# Adafruit_RP2040_CAN_Bus_Feather.net
KiCad netlist of a schematic drawn in EAGLE
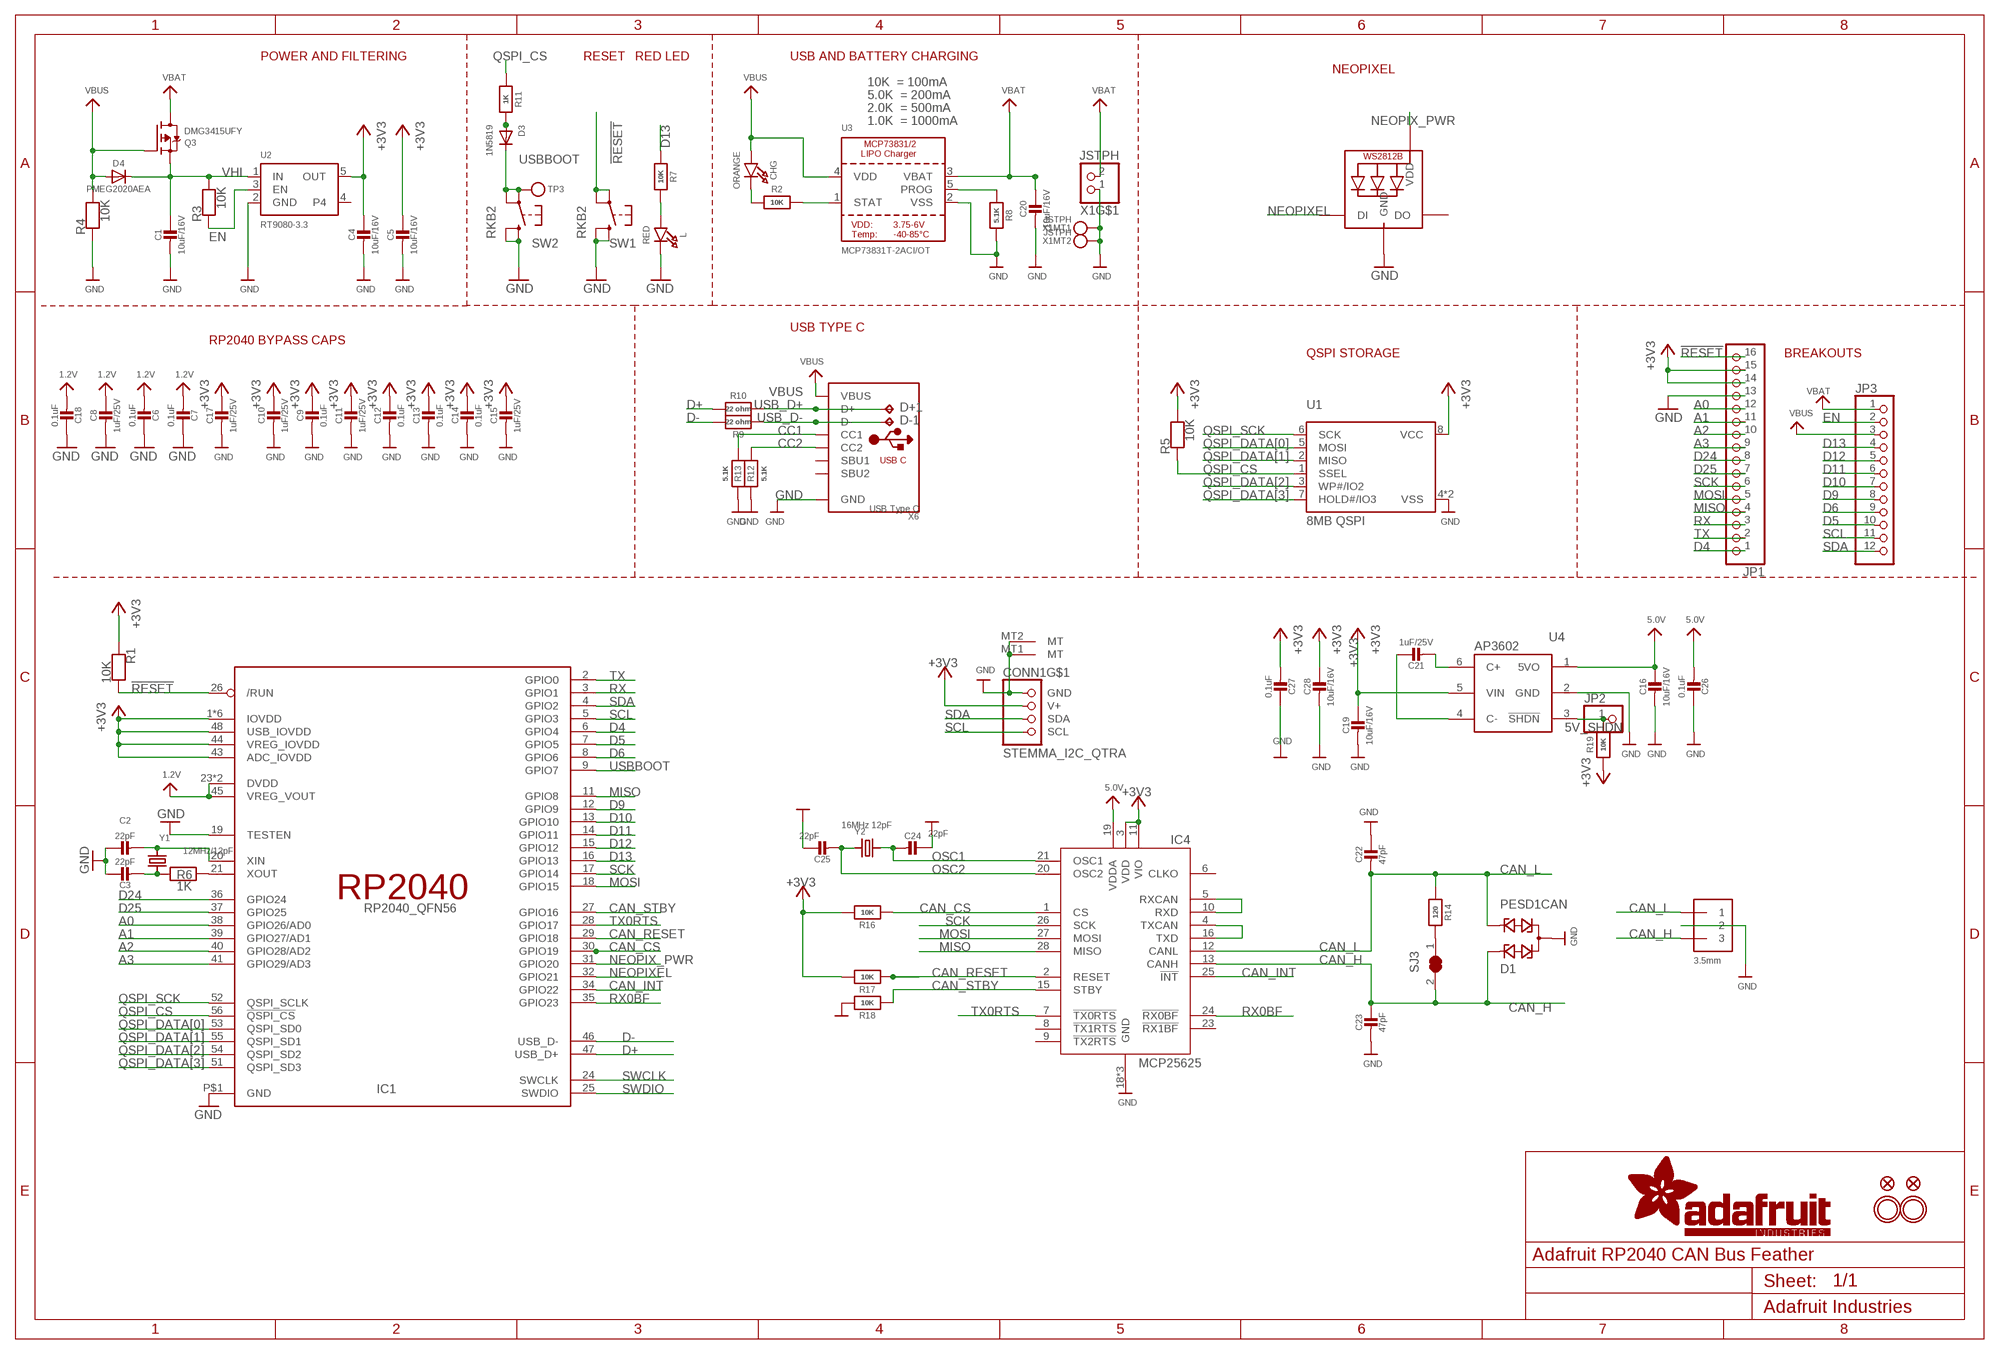
[diagram p0: schematic, sheet 1]

(export (version "E")
  (design (tool "Eeschema 10.0.6"))
  (components
    (comp (ref "C1")
      (value "10uF/16V")
      (footprint "eagle-import:0805-NO")
      (libsource (lib "eagle-import") (part "CAP_CERAMIC0805-NOOUTLINE"))
    )
    (comp (ref "C2")
      (value "22pF")
      (footprint "eagle-import:_0402NO")
      (libsource (lib "eagle-import") (part "CAP_CERAMIC_0402NO"))
    )
    (comp (ref "C3")
      (value "22pF")
      (footprint "eagle-import:_0402NO")
      (libsource (lib "eagle-import") (part "CAP_CERAMIC_0402NO"))
    )
    (comp (ref "C4")
      (value "10uF/16V")
      (footprint "eagle-import:0805-NO")
      (fields (field (name "REV") "A"))
      (libsource (lib "eagle-import") (part "CAP_CERAMIC0805-NOOUTLINE"))
    )
    (comp (ref "C5")
      (value "10uF/16V")
      (footprint "eagle-import:0805-NO")
      (libsource (lib "eagle-import") (part "CAP_CERAMIC0805-NOOUTLINE"))
    )
    (comp (ref "C6")
      (value "0.1uF")
      (footprint "eagle-import:_0402NO")
      (libsource (lib "eagle-import") (part "CAP_CERAMIC_0402NO"))
    )
    (comp (ref "C7")
      (value "0.1uF")
      (footprint "eagle-import:_0402NO")
      (libsource (lib "eagle-import") (part "CAP_CERAMIC_0402NO"))
    )
    (comp (ref "C8")
      (value "1uF/25V")
      (footprint "eagle-import:_0402NO")
      (libsource (lib "eagle-import") (part "CAP_CERAMIC_0402NO"))
    )
    (comp (ref "C9")
      (value "0.1uF")
      (footprint "eagle-import:_0402NO")
      (libsource (lib "eagle-import") (part "CAP_CERAMIC_0402NO"))
    )
    (comp (ref "C10")
      (value "1uF/25V")
      (footprint "eagle-import:_0402NO")
      (libsource (lib "eagle-import") (part "CAP_CERAMIC_0402NO"))
    )
    (comp (ref "C11")
      (value "1uF/25V")
      (footprint "eagle-import:_0402NO")
      (libsource (lib "eagle-import") (part "CAP_CERAMIC_0402NO"))
    )
    (comp (ref "C12")
      (value "0.1uF")
      (footprint "eagle-import:_0402NO")
      (libsource (lib "eagle-import") (part "CAP_CERAMIC_0402NO"))
    )
    (comp (ref "C13")
      (value "0.1uF")
      (footprint "eagle-import:_0402NO")
      (libsource (lib "eagle-import") (part "CAP_CERAMIC_0402NO"))
    )
    (comp (ref "C14")
      (value "0.1uF")
      (footprint "eagle-import:_0402NO")
      (libsource (lib "eagle-import") (part "CAP_CERAMIC_0402NO"))
    )
    (comp (ref "C15")
      (value "1uF/25V")
      (footprint "eagle-import:_0402NO")
      (libsource (lib "eagle-import") (part "CAP_CERAMIC_0402NO"))
    )
    (comp (ref "C16")
      (value "10uF/16V")
      (footprint "eagle-import:0805-NO")
      (libsource (lib "eagle-import") (part "CAP_CERAMIC0805-NOOUTLINE"))
    )
    (comp (ref "C17")
      (value "1uF/25V")
      (footprint "eagle-import:_0402NO")
      (libsource (lib "eagle-import") (part "CAP_CERAMIC_0402NO"))
    )
    (comp (ref "C18")
      (value "0.1uF")
      (footprint "eagle-import:_0402NO")
      (libsource (lib "eagle-import") (part "CAP_CERAMIC_0402NO"))
    )
    (comp (ref "C19")
      (value "10uF/16V")
      (footprint "eagle-import:0805-NO")
      (libsource (lib "eagle-import") (part "CAP_CERAMIC0805-NOOUTLINE"))
    )
    (comp (ref "C20")
      (value "10uF/16V")
      (footprint "eagle-import:0805-NO")
      (libsource (lib "eagle-import") (part "CAP_CERAMIC0805-NOOUTLINE"))
    )
    (comp (ref "C21")
      (value "1uF/25V")
      (footprint "eagle-import:_0402NO")
      (libsource (lib "eagle-import") (part "CAP_CERAMIC_0402NO"))
    )
    (comp (ref "C22")
      (value "47pF")
      (footprint "eagle-import:_0402NO")
      (libsource (lib "eagle-import") (part "CAP_CERAMIC_0402NO"))
    )
    (comp (ref "C23")
      (value "47pF")
      (footprint "eagle-import:_0402NO")
      (libsource (lib "eagle-import") (part "CAP_CERAMIC_0402NO"))
    )
    (comp (ref "C24")
      (value "22pF")
      (footprint "eagle-import:_0402NO")
      (libsource (lib "eagle-import") (part "CAP_CERAMIC_0402NO"))
    )
    (comp (ref "C25")
      (value "22pF")
      (footprint "eagle-import:_0402NO")
      (libsource (lib "eagle-import") (part "CAP_CERAMIC_0402NO"))
    )
    (comp (ref "C26")
      (value "0.1uF")
      (footprint "eagle-import:_0402NO")
      (libsource (lib "eagle-import") (part "CAP_CERAMIC_0402NO"))
    )
    (comp (ref "C27")
      (value "0.1uF")
      (footprint "eagle-import:_0402NO")
      (libsource (lib "eagle-import") (part "CAP_CERAMIC_0402NO"))
    )
    (comp (ref "C28")
      (value "10uF/16V")
      (footprint "eagle-import:0805-NO")
      (libsource (lib "eagle-import") (part "CAP_CERAMIC0805-NOOUTLINE"))
    )
    (comp (ref "CHG")
      (value "ORANGE")
      (footprint "eagle-import:CHIPLED_0603_NOOUTLINE")
      (libsource (lib "eagle-import") (part "LED0603_NOOUTLINE"))
    )
    (comp (ref "CONN1")
      (value "STEMMA_I2C_QTRA")
      (footprint "eagle-import:JST_SH4_RA")
      (libsource (lib "eagle-import") (part "STEMMA_I2C_QTRA"))
    )
    (comp (ref "D+1")
      (value "TPB1,27")
      (footprint "eagle-import:B1,27")
      (libsource (lib "eagle-import") (part "TPB1,27"))
    )
    (comp (ref "D-1")
      (value "TPB1,27")
      (footprint "eagle-import:B1,27")
      (libsource (lib "eagle-import") (part "TPB1,27"))
    )
    (comp (ref "D1")
      (value "PESD1CAN")
      (footprint "eagle-import:SOT23")
      (libsource (lib "eagle-import") (part "PESD1CAN"))
    )
    (comp (ref "D3")
      (value "1N5819")
      (footprint "eagle-import:SOD-323_MINI")
      (libsource (lib "eagle-import") (part "DIODE_SOD323MINI"))
    )
    (comp (ref "D4")
      (value "PMEG2020AEA")
      (footprint "eagle-import:SOD-323F")
      (libsource (lib "eagle-import") (part "DIODESOD-323F"))
    )
    (comp (ref "IC1")
      (value "RP2040_QFN56")
      (footprint "eagle-import:QFN56_7MM_REDUCEDEPAD")
      (libsource (lib "eagle-import") (part "RP2040_QFN56"))
    )
    (comp (ref "IC4")
      (value "MCP25625")
      (footprint "eagle-import:QFN28-ML_6X6MM")
      (libsource (lib "eagle-import") (part "MCP25625"))
    )
    (comp (ref "JP1")
      (value "HEADER-1X16ROUND")
      (footprint "eagle-import:1X16_ROUND")
      (libsource (lib "eagle-import") (part "HEADER-1X16ROUND"))
    )
    (comp (ref "JP2")
      (value "HEADER-1X12MM")
      (footprint "eagle-import:1X01_2MM")
      (libsource (lib "eagle-import") (part "HEADER-1X12MM"))
    )
    (comp (ref "JP3")
      (value "HEADER-1X12")
      (footprint "eagle-import:1X12_ROUND")
      (libsource (lib "eagle-import") (part "HEADER-1X12"))
    )
    (comp (ref "L")
      (value "RED")
      (footprint "eagle-import:CHIPLED_0603_NOOUTLINE")
      (libsource (lib "eagle-import") (part "LED0603_NOOUTLINE"))
    )
    (comp (ref "LED1")
      (value "WS2812B_SK6805_1515")
      (footprint "eagle-import:SK6805_1515")
      (libsource (lib "eagle-import") (part "WS2812B_SK6805_1515"))
    )
    (comp (ref "NEOPIX1")
      (value "3.5mm")
      (footprint "eagle-import:TERMBLOCK_1X3-3.5MM")
      (libsource (lib "eagle-import") (part "TERMBLOCK_1X3"))
    )
    (comp (ref "Q3")
      (value "DMG3415UFY")
      (footprint "eagle-import:DFN2015-3")
      (libsource (lib "eagle-import") (part "MOSFET-P_DFN2015"))
    )
    (comp (ref "R1")
      (value "10K")
      (footprint "eagle-import:_0402NO")
      (libsource (lib "eagle-import") (part "RESISTOR_0402NO"))
    )
    (comp (ref "R2")
      (value "10K")
      (footprint "eagle-import:_0402NO")
      (libsource (lib "eagle-import") (part "RESISTOR_0402NO"))
    )
    (comp (ref "R3")
      (value "10K")
      (footprint "eagle-import:_0402NO")
      (libsource (lib "eagle-import") (part "RESISTOR_0402NO"))
    )
    (comp (ref "R4")
      (value "10K")
      (footprint "eagle-import:_0402NO")
      (libsource (lib "eagle-import") (part "RESISTOR_0402NO"))
    )
    (comp (ref "R5")
      (value "10K")
      (footprint "eagle-import:_0402NO")
      (libsource (lib "eagle-import") (part "RESISTOR_0402NO"))
    )
    (comp (ref "R6")
      (value "1K")
      (footprint "eagle-import:_0402NO")
      (libsource (lib "eagle-import") (part "RESISTOR_0402NO"))
    )
    (comp (ref "R7")
      (value "10K")
      (footprint "eagle-import:_0402NO")
      (libsource (lib "eagle-import") (part "RESISTOR_0402NO"))
    )
    (comp (ref "R8")
      (value "5.1K")
      (footprint "eagle-import:_0402NO")
      (libsource (lib "eagle-import") (part "RESISTOR_0402NO"))
    )
    (comp (ref "R9")
      (value "22 ohm")
      (footprint "eagle-import:_0402NO")
      (libsource (lib "eagle-import") (part "RESISTOR_0402NO"))
    )
    (comp (ref "R10")
      (value "22 ohm")
      (footprint "eagle-import:_0402NO")
      (libsource (lib "eagle-import") (part "RESISTOR_0402NO"))
    )
    (comp (ref "R11")
      (value "1K")
      (footprint "eagle-import:_0402NO")
      (libsource (lib "eagle-import") (part "RESISTOR_0402NO"))
    )
    (comp (ref "R12")
      (value "5.1K")
      (footprint "eagle-import:_0402NO")
      (libsource (lib "eagle-import") (part "RESISTOR_0402NO"))
    )
    (comp (ref "R13")
      (value "5.1K")
      (footprint "eagle-import:_0402NO")
      (libsource (lib "eagle-import") (part "RESISTOR_0402NO"))
    )
    (comp (ref "R14")
      (value "120")
      (footprint "eagle-import:_0402NO")
      (libsource (lib "eagle-import") (part "RESISTOR_0402NO"))
    )
    (comp (ref "R16")
      (value "10K")
      (footprint "eagle-import:_0402NO")
      (libsource (lib "eagle-import") (part "RESISTOR_0402NO"))
    )
    (comp (ref "R17")
      (value "10K")
      (footprint "eagle-import:_0402NO")
      (libsource (lib "eagle-import") (part "RESISTOR_0402NO"))
    )
    (comp (ref "R18")
      (value "10K")
      (footprint "eagle-import:_0402NO")
      (libsource (lib "eagle-import") (part "RESISTOR_0402NO"))
    )
    (comp (ref "R19")
      (value "10K")
      (footprint "eagle-import:_0402NO")
      (libsource (lib "eagle-import") (part "RESISTOR_0402NO"))
    )
    (comp (ref "SJ3")
      (value "SOLDERJUMPER_CLOSED")
      (footprint "eagle-import:SOLDERJUMPER_CLOSEDWIRE")
      (libsource (lib "eagle-import") (part "SOLDERJUMPER_CLOSED"))
    )
    (comp (ref "SW1")
      (value "RKB2")
      (footprint "eagle-import:BTN_RKB2_4.6X2.8")
      (libsource (lib "eagle-import") (part "SWITCH_TACT_SMT_RKB2"))
    )
    (comp (ref "SW2")
      (value "RKB2")
      (footprint "eagle-import:BTN_RKB2_4.6X2.8")
      (libsource (lib "eagle-import") (part "SWITCH_TACT_SMT_RKB2"))
    )
    (comp (ref "TP3")
      (value "TESTPOINTROUND1.5MMNO")
      (footprint "eagle-import:TESTPOINT_ROUND_1.5MM_NO")
      (libsource (lib "eagle-import") (part "TESTPOINTROUND1.5MMNO"))
    )
    (comp (ref "U$31")
      (value "MOUNTINGHOLE2.5")
      (footprint "eagle-import:MOUNTINGHOLE_2.5_PLATED")
      (libsource (lib "eagle-import") (part "MOUNTINGHOLE2.5"))
    )
    (comp (ref "U$32")
      (value "MOUNTINGHOLE2.5")
      (footprint "eagle-import:MOUNTINGHOLE_2.5_PLATED")
      (libsource (lib "eagle-import") (part "MOUNTINGHOLE2.5"))
    )
    (comp (ref "U$34")
      (value "FIDUCIAL_1MM")
      (footprint "eagle-import:FIDUCIAL_1MM")
      (libsource (lib "eagle-import") (part "FIDUCIAL_1MM"))
    )
    (comp (ref "U$35")
      (value "FIDUCIAL_1MM")
      (footprint "eagle-import:FIDUCIAL_1MM")
      (libsource (lib "eagle-import") (part "FIDUCIAL_1MM"))
    )
    (comp (ref "U1")
      (value "8MB QSPI")
      (footprint "eagle-import:USON8_4X4")
      (libsource (lib "eagle-import") (part "SPIFLASH_8PIN_4X4"))
    )
    (comp (ref "U2")
      (value "RT9080-3.3")
      (footprint "eagle-import:SOT23-5")
      (fields (field (name "JLC_ROTATION") "0"))
      (libsource (lib "eagle-import") (part "VREG_SOT23-5"))
    )
    (comp (ref "U3")
      (value "MCP73831T-2ACI/OT")
      (footprint "eagle-import:SOT23-5")
      (libsource (lib "eagle-import") (part "MCP73831/2"))
    )
    (comp (ref "U4")
      (value "AP3602")
      (footprint "eagle-import:SOT23-6")
      (libsource (lib "eagle-import") (part "AP3602"))
    )
    (comp (ref "X1")
      (value "JSTPH")
      (footprint "eagle-import:JSTPH2_BATT")
      (libsource (lib "eagle-import") (part "CON_JST_PH_2PIN_MT_BATT"))
    )
    (comp (ref "X6")
      (value "USB Type C")
      (footprint "eagle-import:USB_C_CUSB31-CFM2AX-01-X")
      (libsource (lib "eagle-import") (part "USB_C"))
    )
    (comp (ref "Y1")
      (value "12MHz/12pF")
      (footprint "eagle-import:CRYSTAL_2.5X2")
      (libsource (lib "eagle-import") (part "CRYSTAL2.5X2.0"))
    )
    (comp (ref "Y2")
      (value "16MHz 12pF")
      (footprint "eagle-import:CRYSTAL_2.5X2")
      (libsource (lib "eagle-import") (part "CRYSTAL2.5X2.0"))
    )
  )
  (nets
    (net (code "1") (name "+3V3") (class "Default")
      (node (ref "C10") (pin "1") (pinfunction "1_1") (pintype "passive"))
      (node (ref "C11") (pin "1") (pinfunction "1_1") (pintype "passive"))
      (node (ref "C12") (pin "1") (pinfunction "1_1") (pintype "passive"))
      (node (ref "C13") (pin "1") (pinfunction "1_1") (pintype "passive"))
      (node (ref "C14") (pin "1") (pinfunction "1_1") (pintype "passive"))
      (node (ref "C15") (pin "1") (pinfunction "1_1") (pintype "passive"))
      (node (ref "C17") (pin "1") (pinfunction "1_1") (pintype "passive"))
      (node (ref "C19") (pin "1") (pinfunction "1_1") (pintype "passive"))
      (node (ref "C27") (pin "2") (pinfunction "2_2") (pintype "passive"))
      (node (ref "C28") (pin "1") (pinfunction "1_1") (pintype "passive"))
      (node (ref "C4") (pin "1") (pinfunction "1_1") (pintype "passive"))
      (node (ref "C5") (pin "1") (pinfunction "1_1") (pintype "passive"))
      (node (ref "C9") (pin "1") (pinfunction "1_1") (pintype "passive"))
      (node (ref "CONN1") (pin "2") (pinfunction "V+_2") (pintype "passive"))
      (node (ref "IC1") (pin "1") (pinfunction "IOVDD_1") (pintype "power_in"))
      (node (ref "IC1") (pin "10") (pinfunction "IOVDD_10") (pintype "power_in"))
      (node (ref "IC1") (pin "22") (pinfunction "IOVDD_22") (pintype "power_in"))
      (node (ref "IC1") (pin "33") (pinfunction "IOVDD_33") (pintype "power_in"))
      (node (ref "IC1") (pin "42") (pinfunction "IOVDD_42") (pintype "power_in"))
      (node (ref "IC1") (pin "43") (pinfunction "ADC_IOVDD_43") (pintype "power_in"))
      (node (ref "IC1") (pin "44") (pinfunction "VREG_IOVDD_44") (pintype "power_in"))
      (node (ref "IC1") (pin "48") (pinfunction "USB_IOVDD_48") (pintype "power_in"))
      (node (ref "IC1") (pin "49") (pinfunction "IOVDD_49") (pintype "power_in"))
      (node (ref "IC4") (pin "11") (pinfunction "VIO_11") (pintype "power_in"))
      (node (ref "IC4") (pin "3") (pinfunction "VDD_3") (pintype "power_in"))
      (node (ref "JP1") (pin "14") (pinfunction "14_14") (pintype "passive"))
      (node (ref "JP1") (pin "15") (pinfunction "15_15") (pintype "passive"))
      (node (ref "R1") (pin "1") (pinfunction "1_1") (pintype "passive"))
      (node (ref "R16") (pin "2") (pinfunction "2_2") (pintype "passive"))
      (node (ref "R17") (pin "2") (pinfunction "2_2") (pintype "passive"))
      (node (ref "R19") (pin "1") (pinfunction "1_1") (pintype "passive"))
      (node (ref "R5") (pin "2") (pinfunction "2_2") (pintype "passive"))
      (node (ref "U1") (pin "8") (pinfunction "VCC_8") (pintype "bidirectional"))
      (node (ref "U2") (pin "5") (pinfunction "OUT_5") (pintype "power_in"))
      (node (ref "U4") (pin "5") (pinfunction "VIN_5") (pintype "power_in"))
    )
    (net (code "2") (name "/5V_SHDN") (class "Default")
      (node (ref "JP2") (pin "1") (pinfunction "1_1") (pintype "passive"))
      (node (ref "R19") (pin "2") (pinfunction "2_2") (pintype "passive"))
      (node (ref "U4") (pin "3") (pinfunction "~{SHDN}_3") (pintype "input"))
    )
    (net (code "3") (name "/A0") (class "Default")
      (node (ref "IC1") (pin "38") (pinfunction "GPIO26/AD0_38") (pintype "bidirectional"))
      (node (ref "JP1") (pin "12") (pinfunction "12_12") (pintype "passive"))
    )
    (net (code "4") (name "/A1") (class "Default")
      (node (ref "IC1") (pin "39") (pinfunction "GPIO27/AD1_39") (pintype "bidirectional"))
      (node (ref "JP1") (pin "11") (pinfunction "11_11") (pintype "passive"))
    )
    (net (code "5") (name "/A2") (class "Default")
      (node (ref "IC1") (pin "40") (pinfunction "GPIO28/AD2_40") (pintype "bidirectional"))
      (node (ref "JP1") (pin "10") (pinfunction "10_10") (pintype "passive"))
    )
    (net (code "6") (name "/A3") (class "Default")
      (node (ref "IC1") (pin "41") (pinfunction "GPIO29/AD3_41") (pintype "bidirectional"))
      (node (ref "JP1") (pin "9") (pinfunction "9_9") (pintype "passive"))
    )
    (net (code "7") (name "/CAN_CS") (class "Default")
      (node (ref "IC1") (pin "30") (pinfunction "GPIO19_30") (pintype "bidirectional"))
      (node (ref "IC4") (pin "1") (pinfunction "CS_1") (pintype "input"))
      (node (ref "R16") (pin "1") (pinfunction "1_1") (pintype "passive"))
    )
    (net (code "8") (name "/CAN_H") (class "Default")
      (node (ref "C23") (pin "1") (pinfunction "1_1") (pintype "passive"))
      (node (ref "D1") (pin "1") (pinfunction "1_1") (pintype "passive"))
      (node (ref "IC4") (pin "13") (pinfunction "CANH_13") (pintype "bidirectional"))
      (node (ref "NEOPIX1") (pin "3") (pinfunction "3_3") (pintype "passive"))
      (node (ref "SJ3") (pin "2") (pinfunction "2_2") (pintype "passive"))
    )
    (net (code "9") (name "/CAN_INT") (class "Default")
      (node (ref "IC1") (pin "34") (pinfunction "GPIO22_34") (pintype "bidirectional"))
      (node (ref "IC4") (pin "25") (pinfunction "~{INT}_25") (pintype "output"))
    )
    (net (code "10") (name "/CAN_L") (class "Default")
      (node (ref "C22") (pin "2") (pinfunction "2_2") (pintype "passive"))
      (node (ref "D1") (pin "2") (pinfunction "2_2") (pintype "passive"))
      (node (ref "IC4") (pin "12") (pinfunction "CANL_12") (pintype "bidirectional"))
      (node (ref "NEOPIX1") (pin "1") (pinfunction "1_1") (pintype "passive"))
      (node (ref "R14") (pin "1") (pinfunction "1_1") (pintype "passive"))
    )
    (net (code "11") (name "/CAN_RESET") (class "Default")
      (node (ref "IC1") (pin "29") (pinfunction "GPIO18_29") (pintype "bidirectional"))
      (node (ref "IC4") (pin "2") (pinfunction "RESET_2") (pintype "input"))
      (node (ref "R17") (pin "1") (pinfunction "1_1") (pintype "passive"))
    )
    (net (code "12") (name "/CAN_STBY") (class "Default")
      (node (ref "IC1") (pin "27") (pinfunction "GPIO16_27") (pintype "bidirectional"))
      (node (ref "IC4") (pin "15") (pinfunction "STBY_15") (pintype "input"))
      (node (ref "R18") (pin "1") (pinfunction "1_1") (pintype "passive"))
    )
    (net (code "13") (name "/CC1") (class "Default")
      (node (ref "R13") (pin "2") (pinfunction "2_2") (pintype "passive"))
      (node (ref "X6") (pin "A5") (pinfunction "CC1_A5") (pintype "bidirectional"))
    )
    (net (code "14") (name "/CC2") (class "Default")
      (node (ref "R12") (pin "2") (pinfunction "2_2") (pintype "passive"))
      (node (ref "X6") (pin "B5") (pinfunction "CC2_B5") (pintype "bidirectional"))
    )
    (net (code "15") (name "/D+") (class "Default")
      (node (ref "IC1") (pin "47") (pinfunction "USB_D+_47") (pintype "bidirectional"))
      (node (ref "R10") (pin "2") (pinfunction "2_2") (pintype "passive"))
    )
    (net (code "16") (name "/D-") (class "Default")
      (node (ref "IC1") (pin "46") (pinfunction "USB_D-_46") (pintype "bidirectional"))
      (node (ref "R9") (pin "2") (pinfunction "2_2") (pintype "passive"))
    )
    (net (code "17") (name "/D4") (class "Default")
      (node (ref "IC1") (pin "6") (pinfunction "GPIO4_6") (pintype "bidirectional"))
      (node (ref "JP1") (pin "1") (pinfunction "1_1") (pintype "passive"))
    )
    (net (code "18") (name "/D5") (class "Default")
      (node (ref "IC1") (pin "7") (pinfunction "GPIO5_7") (pintype "bidirectional"))
      (node (ref "JP3") (pin "10") (pinfunction "10_10") (pintype "passive"))
    )
    (net (code "19") (name "/D6") (class "Default")
      (node (ref "IC1") (pin "8") (pinfunction "GPIO6_8") (pintype "bidirectional"))
      (node (ref "JP3") (pin "9") (pinfunction "9_9") (pintype "passive"))
    )
    (net (code "20") (name "/D9") (class "Default")
      (node (ref "IC1") (pin "12") (pinfunction "GPIO9_12") (pintype "bidirectional"))
      (node (ref "JP3") (pin "8") (pinfunction "8_8") (pintype "passive"))
    )
    (net (code "21") (name "/D10") (class "Default")
      (node (ref "IC1") (pin "13") (pinfunction "GPIO10_13") (pintype "bidirectional"))
      (node (ref "JP3") (pin "7") (pinfunction "7_7") (pintype "passive"))
    )
    (net (code "22") (name "/D11") (class "Default")
      (node (ref "IC1") (pin "14") (pinfunction "GPIO11_14") (pintype "bidirectional"))
      (node (ref "JP3") (pin "6") (pinfunction "6_6") (pintype "passive"))
    )
    (net (code "23") (name "/D12") (class "Default")
      (node (ref "IC1") (pin "15") (pinfunction "GPIO12_15") (pintype "bidirectional"))
      (node (ref "JP3") (pin "5") (pinfunction "5_5") (pintype "passive"))
    )
    (net (code "24") (name "/D13") (class "Default")
      (node (ref "IC1") (pin "16") (pinfunction "GPIO13_16") (pintype "bidirectional"))
      (node (ref "JP3") (pin "4") (pinfunction "4_4") (pintype "passive"))
      (node (ref "R7") (pin "1") (pinfunction "1_1") (pintype "passive"))
    )
    (net (code "25") (name "/D24") (class "Default")
      (node (ref "IC1") (pin "36") (pinfunction "GPIO24_36") (pintype "bidirectional"))
      (node (ref "JP1") (pin "8") (pinfunction "8_8") (pintype "passive"))
    )
    (net (code "26") (name "/D25") (class "Default")
      (node (ref "IC1") (pin "37") (pinfunction "GPIO25_37") (pintype "bidirectional"))
      (node (ref "JP1") (pin "7") (pinfunction "7_7") (pintype "passive"))
    )
    (net (code "27") (name "/EN") (class "Default")
      (node (ref "JP3") (pin "2") (pinfunction "2_2") (pintype "passive"))
      (node (ref "R3") (pin "1") (pinfunction "1_1") (pintype "passive"))
      (node (ref "U2") (pin "3") (pinfunction "EN_3") (pintype "input"))
    )
    (net (code "28") (name "/MISO") (class "Default")
      (node (ref "IC1") (pin "11") (pinfunction "GPIO8_11") (pintype "bidirectional"))
      (node (ref "IC4") (pin "28") (pinfunction "MISO_28") (pintype "output"))
      (node (ref "JP1") (pin "4") (pinfunction "4_4") (pintype "passive"))
    )
    (net (code "29") (name "/MOSI") (class "Default")
      (node (ref "IC1") (pin "18") (pinfunction "GPIO15_18") (pintype "bidirectional"))
      (node (ref "IC4") (pin "27") (pinfunction "MOSI_27") (pintype "input"))
      (node (ref "JP1") (pin "5") (pinfunction "5_5") (pintype "passive"))
    )
    (net (code "30") (name "/NEOPIXEL") (class "Default")
      (node (ref "IC1") (pin "32") (pinfunction "GPIO21_32") (pintype "bidirectional"))
      (node (ref "LED1") (pin "1") (pinfunction "DI_1") (pintype "input"))
    )
    (net (code "31") (name "/NEOPIX_PWR") (class "Default")
      (node (ref "IC1") (pin "31") (pinfunction "GPIO20_31") (pintype "bidirectional"))
      (node (ref "LED1") (pin "2") (pinfunction "VDD_2") (pintype "power_in"))
    )
    (net (code "32") (name "/OSC1") (class "Default")
      (node (ref "C24") (pin "2") (pinfunction "2_2") (pintype "passive"))
      (node (ref "IC4") (pin "21") (pinfunction "OSC1_21") (pintype "input"))
      (node (ref "Y2") (pin "3") (pinfunction "2_3") (pintype "passive"))
    )
    (net (code "33") (name "/OSC2") (class "Default")
      (node (ref "C25") (pin "2") (pinfunction "2_2") (pintype "passive"))
      (node (ref "IC4") (pin "20") (pinfunction "OSC2_20") (pintype "output"))
      (node (ref "Y2") (pin "1") (pinfunction "1_1") (pintype "passive"))
    )
    (net (code "34") (name "/QSPI_CS") (class "Default")
      (node (ref "IC1") (pin "56") (pinfunction "~{QSPI_CS}_56") (pintype "bidirectional"))
      (node (ref "R11") (pin "1") (pinfunction "1_1") (pintype "passive"))
      (node (ref "R5") (pin "1") (pinfunction "1_1") (pintype "passive"))
      (node (ref "U1") (pin "1") (pinfunction "SSEL_1") (pintype "bidirectional"))
    )
    (net (code "35") (name "/QSPI_DATA[0]") (class "Default")
      (node (ref "IC1") (pin "53") (pinfunction "QSPI_SD0_53") (pintype "bidirectional"))
      (node (ref "U1") (pin "5") (pinfunction "MOSI_5") (pintype "bidirectional"))
    )
    (net (code "36") (name "/QSPI_DATA[1]") (class "Default")
      (node (ref "IC1") (pin "55") (pinfunction "QSPI_SD1_55") (pintype "bidirectional"))
      (node (ref "U1") (pin "2") (pinfunction "MISO_2") (pintype "bidirectional"))
    )
    (net (code "37") (name "/QSPI_DATA[2]") (class "Default")
      (node (ref "IC1") (pin "54") (pinfunction "QSPI_SD2_54") (pintype "bidirectional"))
      (node (ref "U1") (pin "3") (pinfunction "WP#/IO2_3") (pintype "bidirectional"))
    )
    (net (code "38") (name "/QSPI_DATA[3]") (class "Default")
      (node (ref "IC1") (pin "51") (pinfunction "QSPI_SD3_51") (pintype "bidirectional"))
      (node (ref "U1") (pin "7") (pinfunction "HOLD#/IO3_7") (pintype "bidirectional"))
    )
    (net (code "39") (name "/QSPI_SCK") (class "Default")
      (node (ref "IC1") (pin "52") (pinfunction "QSPI_SCLK_52") (pintype "bidirectional"))
      (node (ref "U1") (pin "6") (pinfunction "SCK_6") (pintype "bidirectional"))
    )
    (net (code "40") (name "/RX") (class "Default")
      (node (ref "IC1") (pin "3") (pinfunction "GPIO1_3") (pintype "bidirectional"))
      (node (ref "JP1") (pin "3") (pinfunction "3_3") (pintype "passive"))
    )
    (net (code "41") (name "/RX0BF") (class "Default")
      (node (ref "IC1") (pin "35") (pinfunction "GPIO23_35") (pintype "bidirectional"))
      (node (ref "IC4") (pin "24") (pinfunction "~{RX0BF}_24") (pintype "output"))
    )
    (net (code "42") (name "/SCK") (class "Default")
      (node (ref "IC1") (pin "17") (pinfunction "GPIO14_17") (pintype "bidirectional"))
      (node (ref "IC4") (pin "26") (pinfunction "SCK_26") (pintype "input"))
      (node (ref "JP1") (pin "6") (pinfunction "6_6") (pintype "passive"))
    )
    (net (code "43") (name "/SCL") (class "Default")
      (node (ref "CONN1") (pin "4") (pinfunction "SCL_4") (pintype "passive"))
      (node (ref "IC1") (pin "5") (pinfunction "GPIO3_5") (pintype "bidirectional"))
      (node (ref "JP3") (pin "11") (pinfunction "11_11") (pintype "passive"))
    )
    (net (code "44") (name "/SDA") (class "Default")
      (node (ref "CONN1") (pin "3") (pinfunction "SDA_3") (pintype "passive"))
      (node (ref "IC1") (pin "4") (pinfunction "GPIO2_4") (pintype "bidirectional"))
      (node (ref "JP3") (pin "12") (pinfunction "12_12") (pintype "passive"))
    )
    (net (code "45") (name "/SWCLK") (class "Default")
      (node (ref "IC1") (pin "24") (pinfunction "SWCLK_24") (pintype "bidirectional"))
    )
    (net (code "46") (name "/SWDIO") (class "Default")
      (node (ref "IC1") (pin "25") (pinfunction "SWDIO_25") (pintype "bidirectional"))
    )
    (net (code "47") (name "/TX") (class "Default")
      (node (ref "IC1") (pin "2") (pinfunction "GPIO0_2") (pintype "bidirectional"))
      (node (ref "JP1") (pin "2") (pinfunction "2_2") (pintype "passive"))
    )
    (net (code "48") (name "/TX0RTS") (class "Default")
      (node (ref "IC1") (pin "28") (pinfunction "GPIO17_28") (pintype "bidirectional"))
      (node (ref "IC4") (pin "7") (pinfunction "~{TX0RTS}_7") (pintype "input"))
    )
    (net (code "49") (name "/USBBOOT") (class "Default")
      (node (ref "D3") (pin "C") (pinfunction "C_C") (pintype "passive"))
      (node (ref "IC1") (pin "9") (pinfunction "GPIO7_9") (pintype "bidirectional"))
      (node (ref "SW2") (pin "A") (pinfunction "P_A") (pintype "passive"))
      (node (ref "SW2") (pin "A'") (pinfunction "P1_A'") (pintype "passive"))
      (node (ref "TP3") (pin "P$1") (pinfunction "P$1_P$1") (pintype "bidirectional"))
    )
    (net (code "50") (name "/USB_D+") (class "Default")
      (node (ref "D+1") (pin "TP") (pinfunction "TP_TP") (pintype "input"))
      (node (ref "R10") (pin "1") (pinfunction "1_1") (pintype "passive"))
      (node (ref "X6") (pin "A6") (pinfunction "D+_A6") (pintype "bidirectional"))
      (node (ref "X6") (pin "B6") (pinfunction "D+_B6") (pintype "bidirectional"))
    )
    (net (code "51") (name "/USB_D-") (class "Default")
      (node (ref "D-1") (pin "TP") (pinfunction "TP_TP") (pintype "input"))
      (node (ref "R9") (pin "1") (pinfunction "1_1") (pintype "passive"))
      (node (ref "X6") (pin "A7") (pinfunction "D-_A7") (pintype "bidirectional"))
      (node (ref "X6") (pin "B7") (pinfunction "D-_B7") (pintype "bidirectional"))
    )
    (net (code "52") (name "/VHI") (class "Default")
      (node (ref "C1") (pin "1") (pinfunction "1_1") (pintype "passive"))
      (node (ref "D4") (pin "C") (pinfunction "C_C") (pintype "passive"))
      (node (ref "Q3") (pin "2") (pinfunction "S_2") (pintype "passive"))
      (node (ref "R3") (pin "2") (pinfunction "2_2") (pintype "passive"))
      (node (ref "U2") (pin "1") (pinfunction "IN_1") (pintype "power_in"))
    )
    (net (code "53") (name "/~{RESET}") (class "Default")
      (node (ref "IC1") (pin "26") (pinfunction "/RUN_26") (pintype "bidirectional"))
      (node (ref "JP1") (pin "16") (pinfunction "16_16") (pintype "passive"))
      (node (ref "R1") (pin "2") (pinfunction "2_2") (pintype "passive"))
      (node (ref "SW1") (pin "A") (pinfunction "P_A") (pintype "passive"))
      (node (ref "SW1") (pin "A'") (pinfunction "P1_A'") (pintype "passive"))
    )
    (net (code "54") (name "1.2V") (class "Default")
      (node (ref "C18") (pin "2") (pinfunction "2_2") (pintype "passive"))
      (node (ref "C6") (pin "2") (pinfunction "2_2") (pintype "passive"))
      (node (ref "C7") (pin "2") (pinfunction "2_2") (pintype "passive"))
      (node (ref "C8") (pin "1") (pinfunction "1_1") (pintype "passive"))
      (node (ref "IC1") (pin "23") (pinfunction "DVDD_23") (pintype "power_in"))
      (node (ref "IC1") (pin "45") (pinfunction "VREG_VOUT_45") (pintype "power_in"))
      (node (ref "IC1") (pin "50") (pinfunction "DVDD_50") (pintype "power_in"))
    )
    (net (code "55") (name "5.0V") (class "Default")
      (node (ref "C16") (pin "1") (pinfunction "1_1") (pintype "passive"))
      (node (ref "C26") (pin "2") (pinfunction "2_2") (pintype "passive"))
      (node (ref "IC4") (pin "19") (pinfunction "VDDA_19") (pintype "power_in"))
      (node (ref "U4") (pin "1") (pinfunction "5VO_1") (pintype "power_in"))
    )
    (net (code "56") (name "GND") (class "Default")
      (node (ref "C1") (pin "2") (pinfunction "2_2") (pintype "passive"))
      (node (ref "C10") (pin "2") (pinfunction "2_2") (pintype "passive"))
      (node (ref "C11") (pin "2") (pinfunction "2_2") (pintype "passive"))
      (node (ref "C12") (pin "2") (pinfunction "2_2") (pintype "passive"))
      (node (ref "C13") (pin "2") (pinfunction "2_2") (pintype "passive"))
      (node (ref "C14") (pin "2") (pinfunction "2_2") (pintype "passive"))
      (node (ref "C15") (pin "2") (pinfunction "2_2") (pintype "passive"))
      (node (ref "C16") (pin "2") (pinfunction "2_2") (pintype "passive"))
      (node (ref "C17") (pin "2") (pinfunction "2_2") (pintype "passive"))
      (node (ref "C18") (pin "1") (pinfunction "1_1") (pintype "passive"))
      (node (ref "C19") (pin "2") (pinfunction "2_2") (pintype "passive"))
      (node (ref "C2") (pin "1") (pinfunction "1_1") (pintype "passive"))
      (node (ref "C20") (pin "2") (pinfunction "2_2") (pintype "passive"))
      (node (ref "C22") (pin "1") (pinfunction "1_1") (pintype "passive"))
      (node (ref "C23") (pin "2") (pinfunction "2_2") (pintype "passive"))
      (node (ref "C24") (pin "1") (pinfunction "1_1") (pintype "passive"))
      (node (ref "C25") (pin "1") (pinfunction "1_1") (pintype "passive"))
      (node (ref "C26") (pin "1") (pinfunction "1_1") (pintype "passive"))
      (node (ref "C27") (pin "1") (pinfunction "1_1") (pintype "passive"))
      (node (ref "C28") (pin "2") (pinfunction "2_2") (pintype "passive"))
      (node (ref "C3") (pin "1") (pinfunction "1_1") (pintype "passive"))
      (node (ref "C4") (pin "2") (pinfunction "2_2") (pintype "passive"))
      (node (ref "C5") (pin "2") (pinfunction "2_2") (pintype "passive"))
      (node (ref "C6") (pin "1") (pinfunction "1_1") (pintype "passive"))
      (node (ref "C7") (pin "1") (pinfunction "1_1") (pintype "passive"))
      (node (ref "C8") (pin "2") (pinfunction "2_2") (pintype "passive"))
      (node (ref "C9") (pin "2") (pinfunction "2_2") (pintype "passive"))
      (node (ref "CONN1") (pin "1") (pinfunction "GND_1") (pintype "passive"))
      (node (ref "CONN1") (pin "MT1") (pinfunction "MT_MT1") (pintype "bidirectional"))
      (node (ref "CONN1") (pin "MT2") (pinfunction "MT_MT2") (pintype "bidirectional"))
      (node (ref "D1") (pin "3") (pinfunction "3_3") (pintype "passive"))
      (node (ref "IC1") (pin "19") (pinfunction "TESTEN_19") (pintype "input"))
      (node (ref "IC1") (pin "P$1") (pinfunction "GND_P$1") (pintype "power_in"))
      (node (ref "IC4") (pin "18") (pinfunction "GND_18") (pintype "power_in"))
      (node (ref "IC4") (pin "22") (pinfunction "GND_22") (pintype "power_in"))
      (node (ref "IC4") (pin "EXP") (pinfunction "GND_EXP") (pintype "power_in"))
      (node (ref "JP1") (pin "13") (pinfunction "13_13") (pintype "passive"))
      (node (ref "L") (pin "C") (pinfunction "C_C") (pintype "passive"))
      (node (ref "LED1") (pin "4") (pinfunction "GND_4") (pintype "power_in"))
      (node (ref "NEOPIX1") (pin "2") (pinfunction "2_2") (pintype "passive"))
      (node (ref "R12") (pin "1") (pinfunction "1_1") (pintype "passive"))
      (node (ref "R13") (pin "1") (pinfunction "1_1") (pintype "passive"))
      (node (ref "R18") (pin "2") (pinfunction "2_2") (pintype "passive"))
      (node (ref "R4") (pin "1") (pinfunction "1_1") (pintype "passive"))
      (node (ref "R8") (pin "2") (pinfunction "2_2") (pintype "passive"))
      (node (ref "SW1") (pin "B") (pinfunction "S_B") (pintype "passive"))
      (node (ref "SW1") (pin "B'") (pinfunction "S1_B'") (pintype "passive"))
      (node (ref "SW2") (pin "B") (pinfunction "S_B") (pintype "passive"))
      (node (ref "SW2") (pin "B'") (pinfunction "S1_B'") (pintype "passive"))
      (node (ref "U1") (pin "4") (pinfunction "VSS_4") (pintype "bidirectional"))
      (node (ref "U1") (pin "PAD") (pinfunction "VSS_PAD") (pintype "bidirectional"))
      (node (ref "U2") (pin "2") (pinfunction "GND_2") (pintype "power_in"))
      (node (ref "U3") (pin "2") (pinfunction "VSS_2") (pintype "power_in"))
      (node (ref "U4") (pin "2") (pinfunction "GND_2") (pintype "power_in"))
      (node (ref "X1") (pin "1") (pinfunction "1_1") (pintype "passive"))
      (node (ref "X1") (pin "NC1") (pinfunction "P$1_NC1") (pintype "bidirectional"))
      (node (ref "X1") (pin "NC2") (pinfunction "P$1_NC2") (pintype "bidirectional"))
      (node (ref "X6") (pin "A1B12") (pinfunction "GND_A1B12") (pintype "power_in"))
      (node (ref "X6") (pin "B1A12") (pinfunction "GND_B1A12") (pintype "power_in"))
    )
    (net (code "57") (name "Net-(C3-Pad2)") (class "Default")
      (node (ref "C3") (pin "2") (pinfunction "2_2") (pintype "passive"))
      (node (ref "R6") (pin "1") (pinfunction "1_1") (pintype "passive"))
      (node (ref "Y1") (pin "1") (pinfunction "1_1") (pintype "passive"))
    )
    (net (code "58") (name "Net-(CHG-PadC)") (class "Default")
      (node (ref "CHG") (pin "C") (pinfunction "C_C") (pintype "passive"))
      (node (ref "R2") (pin "1") (pinfunction "1_1") (pintype "passive"))
    )
    (net (code "59") (name "Net-(D3-PadA)") (class "Default")
      (node (ref "D3") (pin "A") (pinfunction "A_A") (pintype "passive"))
      (node (ref "R11") (pin "2") (pinfunction "2_2") (pintype "passive"))
    )
    (net (code "60") (name "Net-(IC1-XIN)") (class "Default")
      (node (ref "C2") (pin "2") (pinfunction "2_2") (pintype "passive"))
      (node (ref "IC1") (pin "20") (pinfunction "XIN_20") (pintype "input"))
      (node (ref "Y1") (pin "3") (pinfunction "2_3") (pintype "passive"))
    )
    (net (code "61") (name "Net-(IC1-XOUT)") (class "Default")
      (node (ref "IC1") (pin "21") (pinfunction "XOUT_21") (pintype "output"))
      (node (ref "R6") (pin "2") (pinfunction "2_2") (pintype "passive"))
    )
    (net (code "62") (name "Net-(IC4-RXCAN)") (class "Default")
      (node (ref "IC4") (pin "10") (pinfunction "RXD_10") (pintype "output"))
      (node (ref "IC4") (pin "5") (pinfunction "RXCAN_5") (pintype "input"))
    )
    (net (code "63") (name "Net-(IC4-TXCAN)") (class "Default")
      (node (ref "IC4") (pin "16") (pinfunction "TXD_16") (pintype "input"))
      (node (ref "IC4") (pin "4") (pinfunction "TXCAN_4") (pintype "output"))
    )
    (net (code "64") (name "Net-(L-PadA)") (class "Default")
      (node (ref "L") (pin "A") (pinfunction "A_A") (pintype "passive"))
      (node (ref "R7") (pin "2") (pinfunction "2_2") (pintype "passive"))
    )
    (net (code "65") (name "Net-(R14-Pad2)") (class "Default")
      (node (ref "R14") (pin "2") (pinfunction "2_2") (pintype "passive"))
      (node (ref "SJ3") (pin "1") (pinfunction "1_1") (pintype "passive"))
    )
    (net (code "66") (name "Net-(U3-PROG)") (class "Default")
      (node (ref "R8") (pin "1") (pinfunction "1_1") (pintype "passive"))
      (node (ref "U3") (pin "5") (pinfunction "PROG_5") (pintype "input"))
    )
    (net (code "67") (name "Net-(U3-STAT)") (class "Default")
      (node (ref "R2") (pin "2") (pinfunction "2_2") (pintype "passive"))
      (node (ref "U3") (pin "1") (pinfunction "STAT_1") (pintype "output"))
    )
    (net (code "68") (name "Net-(U4-C+)") (class "Default")
      (node (ref "C21") (pin "2") (pinfunction "2_2") (pintype "passive"))
      (node (ref "U4") (pin "6") (pinfunction "C+_6") (pintype "bidirectional"))
    )
    (net (code "69") (name "Net-(U4-C-)") (class "Default")
      (node (ref "C21") (pin "1") (pinfunction "1_1") (pintype "passive"))
      (node (ref "U4") (pin "4") (pinfunction "C-_4") (pintype "bidirectional"))
    )
    (net (code "70") (name "VBAT") (class "Default")
      (node (ref "C20") (pin "1") (pinfunction "1_1") (pintype "passive"))
      (node (ref "JP3") (pin "1") (pinfunction "1_1") (pintype "passive"))
      (node (ref "Q3") (pin "3") (pinfunction "D_3") (pintype "passive"))
      (node (ref "U3") (pin "3") (pinfunction "VBAT_3") (pintype "power_in"))
      (node (ref "X1") (pin "2") (pinfunction "2_2") (pintype "passive"))
    )
    (net (code "71") (name "VBUS") (class "Default")
      (node (ref "CHG") (pin "A") (pinfunction "A_A") (pintype "passive"))
      (node (ref "D4") (pin "A") (pinfunction "A_A") (pintype "passive"))
      (node (ref "JP3") (pin "3") (pinfunction "3_3") (pintype "passive"))
      (node (ref "Q3") (pin "1") (pinfunction "G_1") (pintype "passive"))
      (node (ref "R4") (pin "2") (pinfunction "2_2") (pintype "passive"))
      (node (ref "U3") (pin "4") (pinfunction "VDD_4") (pintype "power_in"))
      (node (ref "X6") (pin "A4B9") (pinfunction "VBUS_A4B9") (pintype "power_in"))
      (node (ref "X6") (pin "B4A9") (pinfunction "VBUS_B4A9") (pintype "power_in"))
    )
    (net (code "72") (name "unconnected-(IC4-CLKO-Pad6)") (class "Default")
      (node (ref "IC4") (pin "6") (pinfunction "CLKO_6") (pintype "output"))
    )
    (net (code "73") (name "unconnected-(IC4-~{RX1BF}-Pad23)") (class "Default")
      (node (ref "IC4") (pin "23") (pinfunction "~{RX1BF}_23") (pintype "output"))
    )
    (net (code "74") (name "unconnected-(IC4-~{TX1RTS}-Pad8)") (class "Default")
      (node (ref "IC4") (pin "8") (pinfunction "~{TX1RTS}_8") (pintype "input"))
    )
    (net (code "75") (name "unconnected-(IC4-~{TX2RTS}-Pad9)") (class "Default")
      (node (ref "IC4") (pin "9") (pinfunction "~{TX2RTS}_9") (pintype "input"))
    )
    (net (code "76") (name "unconnected-(LED1-DO-Pad3)") (class "Default")
      (node (ref "LED1") (pin "3") (pinfunction "DO_3") (pintype "output"))
    )
    (net (code "77") (name "unconnected-(U2-P4-Pad4)") (class "Default")
      (node (ref "U2") (pin "4") (pinfunction "P4_4") (pintype "bidirectional"))
    )
    (net (code "78") (name "unconnected-(X6-SBU1-PadA8)") (class "Default")
      (node (ref "X6") (pin "A8") (pinfunction "SBU1_A8") (pintype "bidirectional"))
    )
    (net (code "79") (name "unconnected-(X6-SBU2-PadB8)") (class "Default")
      (node (ref "X6") (pin "B8") (pinfunction "SBU2_B8") (pintype "bidirectional"))
    )
  )
)
